# MT3608-dip-board.net
KiCad netlist of a schematic drawn in EAGLE
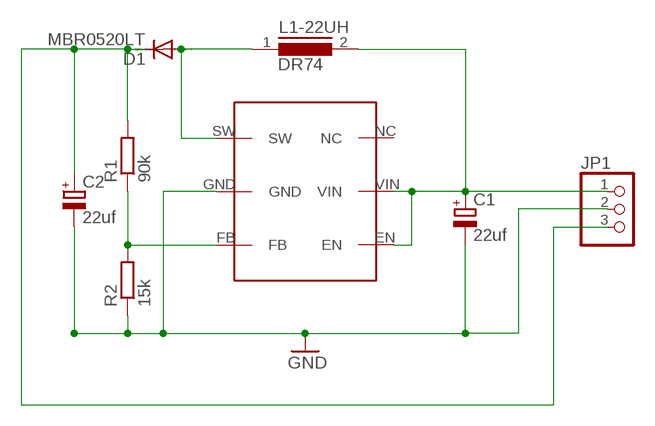
[diagram p0: schematic, sheet 1]

(export (version "E")
  (design (tool "Eeschema 10.0.6"))
  (components
    (comp (ref "C1")
      (value "22uf")
      (footprint "eagle-import:C_6032-28R")
      (libsource (lib "eagle-import") (part "CPOL-EUC/6032-28R"))
    )
    (comp (ref "C2")
      (value "22uf")
      (footprint "eagle-import:C_6032-28R")
      (libsource (lib "eagle-import") (part "CPOL-EUC/6032-28R"))
    )
    (comp (ref "D1")
      (value "MBR0520LT")
      (footprint "eagle-import:SOD123")
      (libsource (lib "eagle-import") (part "MBR0520LT"))
    )
    (comp (ref "JP1")
      (value "PINHD-1X3")
      (footprint "eagle-import:1X03")
      (libsource (lib "eagle-import") (part "PINHD-1X3"))
    )
    (comp (ref "L1-22UH")
      (value "DR74")
      (footprint "eagle-import:DR74")
      (libsource (lib "eagle-import") (part "DR74"))
    )
    (comp (ref "R1")
      (value "90k")
      (footprint "eagle-import:R0805")
      (libsource (lib "eagle-import") (part "R-EU_R0805"))
    )
    (comp (ref "R2")
      (value "15k")
      (footprint "eagle-import:R0805")
      (libsource (lib "eagle-import") (part "R-EU_R0805"))
    )
    (comp (ref "U$1")
      (value "MT3608")
      (footprint "eagle-import:MT3608")
      (libsource (lib "eagle-import") (part "MT3608"))
    )
  )
  (nets
    (net (code "1") (name "GND") (class "Default")
      (node (ref "C1") (pin "-") (pinfunction "-_-") (pintype "passive"))
      (node (ref "C2") (pin "-") (pinfunction "-_-") (pintype "passive"))
      (node (ref "JP1") (pin "2") (pinfunction "2_2") (pintype "passive"))
      (node (ref "R2") (pin "1") (pinfunction "1_1") (pintype "passive"))
      (node (ref "U$1") (pin "GND") (pinfunction "GND_GND") (pintype "bidirectional"))
    )
    (net (code "2") (name "Net-(C1-Pad+)") (class "Default")
      (node (ref "C1") (pin "+") (pinfunction "+_+") (pintype "passive"))
      (node (ref "JP1") (pin "1") (pinfunction "1_1") (pintype "passive"))
      (node (ref "L1-22UH") (pin "2") (pinfunction "2_2") (pintype "passive"))
      (node (ref "U$1") (pin "EN") (pinfunction "EN_EN") (pintype "bidirectional"))
      (node (ref "U$1") (pin "VIN") (pinfunction "VIN_VIN") (pintype "bidirectional"))
    )
    (net (code "3") (name "Net-(C2-Pad+)") (class "Default")
      (node (ref "C2") (pin "+") (pinfunction "+_+") (pintype "passive"))
      (node (ref "D1") (pin "C") (pinfunction "C_C") (pintype "passive"))
      (node (ref "JP1") (pin "3") (pinfunction "3_3") (pintype "passive"))
      (node (ref "R1") (pin "2") (pinfunction "2_2") (pintype "passive"))
    )
    (net (code "4") (name "Net-(D1-PadA)") (class "Default")
      (node (ref "D1") (pin "A") (pinfunction "A_A") (pintype "passive"))
      (node (ref "L1-22UH") (pin "1") (pinfunction "1_1") (pintype "passive"))
      (node (ref "U$1") (pin "SW") (pinfunction "SW_SW") (pintype "bidirectional"))
    )
    (net (code "5") (name "Net-(R1-Pad1)") (class "Default")
      (node (ref "R1") (pin "1") (pinfunction "1_1") (pintype "passive"))
      (node (ref "R2") (pin "2") (pinfunction "2_2") (pintype "passive"))
      (node (ref "U$1") (pin "FB") (pinfunction "FB_FB") (pintype "bidirectional"))
    )
    (net (code "6") (name "unconnected-(U$1-PadNC)") (class "Default")
      (node (ref "U$1") (pin "NC") (pinfunction "NC_NC") (pintype "bidirectional"))
    )
  )
)
